# sensor_v60.net
KiCad netlist of a schematic drawn in EAGLE
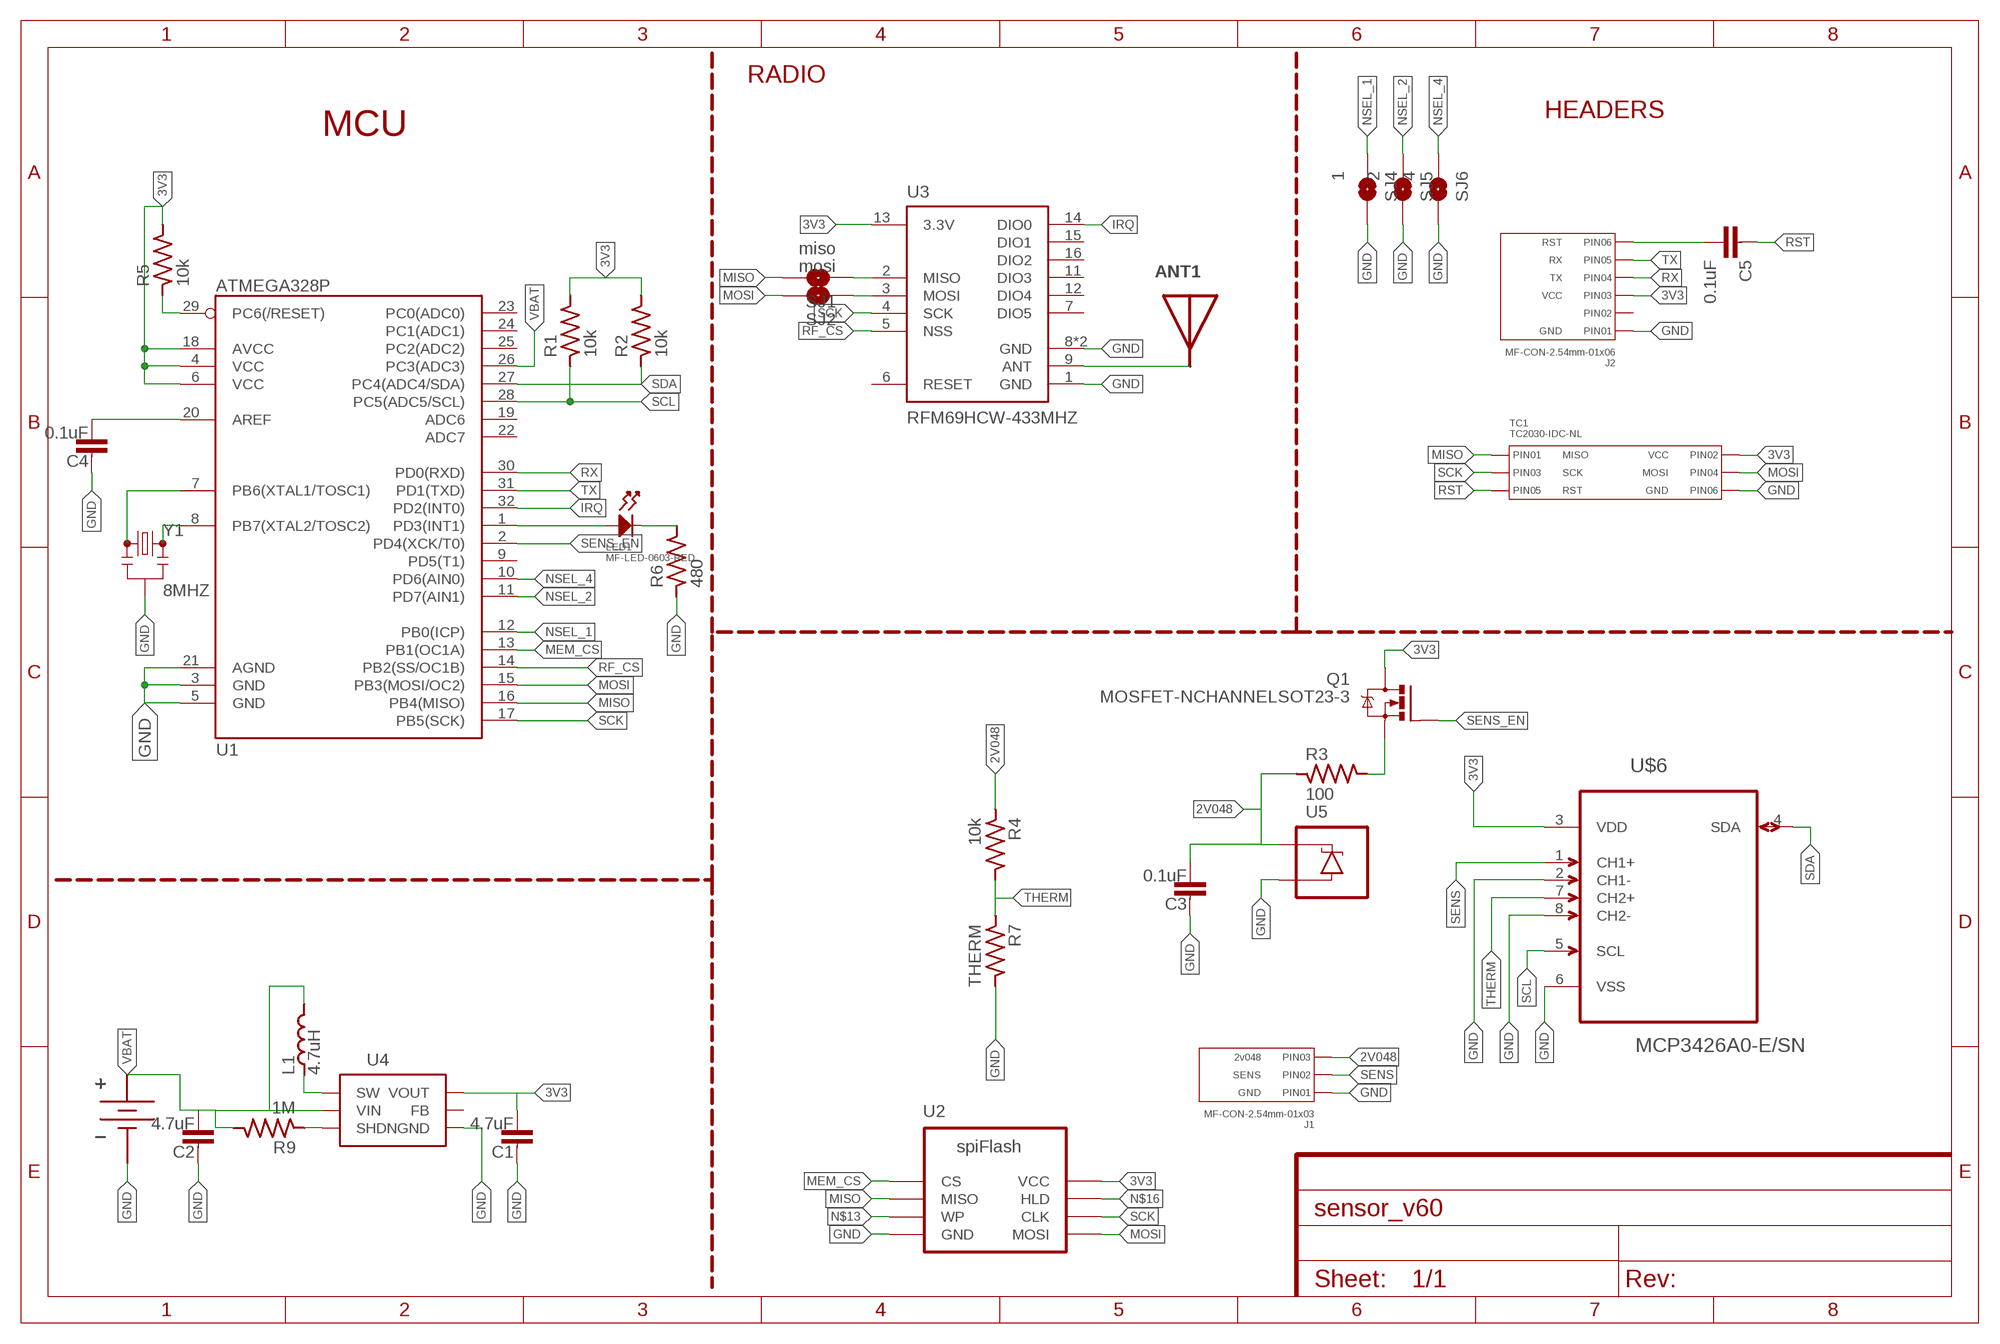
[diagram p0: schematic, sheet 1]

(export (version "E")
  (design (tool "Eeschema 10.0.6"))
  (components
    (comp (ref "ANT1")
      (value "ANTENNA-433_CHIP")
      (footprint "eagle-import:ANT_433_CHIP")
      (fields (field (name "PARTNO") "0433AT62A0020E"))
      (libsource (lib "eagle-import") (part "ANTENNA-433_CHIP"))
    )
    (comp (ref "C1")
      (value "4.7uF")
      (footprint "eagle-import:C0603-N")
      (libsource (lib "eagle-import") (part "CAPACITOR_NP0603-N"))
    )
    (comp (ref "C2")
      (value "4.7uF")
      (footprint "eagle-import:C0603-N")
      (libsource (lib "eagle-import") (part "CAPACITOR_NP0603-N"))
    )
    (comp (ref "C3")
      (value "0.1uF")
      (footprint "eagle-import:C0603-N")
      (libsource (lib "eagle-import") (part "CAPACITOR_NP0603-N"))
    )
    (comp (ref "C4")
      (value "0.1uF")
      (footprint "eagle-import:C0603-N")
      (libsource (lib "eagle-import") (part "CAPACITOR_NP0603-N"))
    )
    (comp (ref "C5")
      (value "0.1uF")
      (footprint "eagle-import:C0603-N")
      (libsource (lib "eagle-import") (part "CAPACITOR0603-N"))
    )
    (comp (ref "J1")
      (value "MF-CON-2.54mm-01x03")
      (footprint "eagle-import:PTH_2.54MM_01X03")
      (fields
        (field (name "HOUSEPART") "YES")
        (field (name "LABEL01") "GND")
        (field (name "LABEL02") "SENS")
        (field (name "LABEL03") "2v048")
        (field (name "PARTNO") "0022053031")
      )
      (libsource (lib "eagle-import") (part "CON_01X03_PTH_2.54MM"))
    )
    (comp (ref "J2")
      (value "MF-CON-2.54mm-01x06")
      (footprint "eagle-import:PTH_2.54MM_01X06")
      (fields
        (field (name "HOUSEPART") "YES")
        (field (name "LABEL01") "GND")
        (field (name "LABEL03") "VCC")
        (field (name "LABEL04") "TX")
        (field (name "LABEL05") "RX")
        (field (name "LABEL06") "RST")
      )
      (libsource (lib "eagle-import") (part "CON_01X06_PTH_2.54MM"))
    )
    (comp (ref "L1")
      (value "4.7uH")
      (footprint "eagle-import:L3030")
      (libsource (lib "eagle-import") (part "INDUCTOR3030"))
    )
    (comp (ref "LED1")
      (value "MF-LED-0603-RED")
      (footprint "eagle-import:LED0603")
      (fields (field (name "HOUSEPART") "YES"))
      (libsource (lib "eagle-import") (part "LED_SINGLE-0603-RED"))
    )
    (comp (ref "Q1")
      (value "MOSFET-NCHANNELSOT23-3")
      (footprint "eagle-import:SOT23-3")
      (libsource (lib "eagle-import") (part "MOSFET-NCHANNELSOT23-3"))
    )
    (comp (ref "R1")
      (value "10k")
      (footprint "eagle-import:R0603-N")
      (libsource (lib "eagle-import") (part "RESISTOR0603-N"))
    )
    (comp (ref "R2")
      (value "10k")
      (footprint "eagle-import:R0603-N")
      (libsource (lib "eagle-import") (part "RESISTOR0603-N"))
    )
    (comp (ref "R3")
      (value "100")
      (footprint "eagle-import:R0603-N")
      (libsource (lib "eagle-import") (part "RESISTOR0603-N"))
    )
    (comp (ref "R4")
      (value "10k")
      (footprint "eagle-import:R0603-N")
      (libsource (lib "eagle-import") (part "RESISTOR0603-N"))
    )
    (comp (ref "R5")
      (value "10k")
      (footprint "eagle-import:R0603-N")
      (libsource (lib "eagle-import") (part "RESISTOR0603-N"))
    )
    (comp (ref "R6")
      (value "480")
      (footprint "eagle-import:R0603-N")
      (libsource (lib "eagle-import") (part "RESISTOR0603-N"))
    )
    (comp (ref "R7")
      (value "THERM")
      (footprint "eagle-import:R0603-N")
      (fields (field (name "PARTNO") "FIND PART!!"))
      (libsource (lib "eagle-import") (part "RESISTOR0603-N"))
    )
    (comp (ref "R9")
      (value "1M")
      (footprint "eagle-import:R0603-N")
      (libsource (lib "eagle-import") (part "RESISTOR0603-N"))
    )
    (comp (ref "SJ1")
      (value "miso")
      (footprint "eagle-import:SJ_2S-NOTRACE")
      (libsource (lib "eagle-import") (part "SOLDERJUMPERNC2"))
    )
    (comp (ref "SJ2")
      (value "mosi")
      (footprint "eagle-import:SJ_2S-NOTRACE")
      (libsource (lib "eagle-import") (part "SOLDERJUMPERNC2"))
    )
    (comp (ref "SJ4")
      (value "1")
      (footprint "eagle-import:SJ_2S-NOTRACE")
      (libsource (lib "eagle-import") (part "SOLDERJUMPERNC2"))
    )
    (comp (ref "SJ5")
      (value "2")
      (footprint "eagle-import:SJ_2S-NOTRACE")
      (libsource (lib "eagle-import") (part "SOLDERJUMPERNC2"))
    )
    (comp (ref "SJ6")
      (value "4")
      (footprint "eagle-import:SJ_2S-NOTRACE")
      (libsource (lib "eagle-import") (part "SOLDERJUMPERNC2"))
    )
    (comp (ref "TC1")
      (value "TC2030-IDC-NL")
      (footprint "eagle-import:TC2030-IDC-NL")
      (fields (field (name "HOUSEPART") "NO") (field (name "PARTNO") "NA"))
      (libsource (lib "eagle-import") (part "CON_02X03_TC2030-IDC-NL_AVRISP"))
    )
    (comp (ref "U$1")
      (value "KEYSTONEAAHOLDER_2CELL")
      (footprint "eagle-import:KEYSTONEAAHOLDER_2CELL")
      (libsource (lib "eagle-import") (part "KEYSTONEAAHOLDER_2CELL"))
    )
    (comp (ref "U$6")
      (value "MCP3426A0-E/SN")
      (footprint "eagle-import:SOIC127P600X175-8N")
      (libsource (lib "eagle-import") (part "MCP3426A0-E/SN"))
    )
    (comp (ref "U1")
      (value "ATMEGA328P")
      (footprint "eagle-import:TQFP32")
      (libsource (lib "eagle-import") (part "ATMEGA328P_SMD-AU"))
    )
    (comp (ref "U2")
      (value "WINBOND_FLASH_4MBIT-SOIC")
      (footprint "eagle-import:SOIC8")
      (libsource (lib "eagle-import") (part "WINBOND_FLASH_4MBIT-SOIC"))
    )
    (comp (ref "U3")
      (value "RFM69HCW-433MHZ")
      (footprint "eagle-import:RFM69HCW-XXXS2")
      (fields (field (name "PARTNO") "COM-13910"))
      (libsource (lib "eagle-import") (part "RFM69HCW-433MHZ"))
    )
    (comp (ref "U4")
      (value "AAT1217-SOT23-6")
      (footprint "eagle-import:SOT23-6")
      (fields (field (name "PARTNO") "AAT1217ICA-3.3-T1"))
      (libsource (lib "eagle-import") (part "AAT1217-SOT23-6"))
    )
    (comp (ref "U5")
      (value "LM4040-SOT-23-3")
      (footprint "eagle-import:SOT23-3")
      (fields (field (name "PARTNO") "LM4040AIM3-2.0/NOPB "))
      (libsource (lib "eagle-import") (part "LM4040-SOT-23-3"))
    )
    (comp (ref "Y1")
      (value "8MHZ")
      (footprint "eagle-import:RESONATOR-SMD")
      (fields (field (name "PARTNO") "CSTCE8M00G55-R0"))
      (libsource (lib "eagle-import") (part "RESONATOR8MHZ"))
    )
  )
  (nets
    (net (code "1") (name "2V048") (class "Default")
      (node (ref "C3") (pin "2") (pinfunction "2_2") (pintype "passive"))
      (node (ref "J1") (pin "P$3") (pinfunction "PIN3_P$3") (pintype "bidirectional"))
      (node (ref "R3") (pin "1") (pinfunction "P$1_1") (pintype "passive"))
      (node (ref "R4") (pin "1") (pinfunction "P$1_1") (pintype "passive"))
      (node (ref "U5") (pin "1") (pinfunction "C_1") (pintype "bidirectional"))
    )
    (net (code "2") (name "3V3") (class "Default")
      (node (ref "C1") (pin "2") (pinfunction "2_2") (pintype "passive"))
      (node (ref "J2") (pin "P$3") (pinfunction "PIN3_P$3") (pintype "bidirectional"))
      (node (ref "Q1") (pin "3") (pinfunction "D_3") (pintype "passive"))
      (node (ref "R1") (pin "2") (pinfunction "P$2_2") (pintype "passive"))
      (node (ref "R2") (pin "2") (pinfunction "P$2_2") (pintype "passive"))
      (node (ref "R5") (pin "2") (pinfunction "P$2_2") (pintype "passive"))
      (node (ref "TC1") (pin "P$2") (pinfunction "PIN2_P$2") (pintype "bidirectional"))
      (node (ref "U$6") (pin "3") (pinfunction "VDD_3") (pintype "power_in"))
      (node (ref "U1") (pin "18") (pinfunction "AVCC_18") (pintype "bidirectional"))
      (node (ref "U1") (pin "4") (pinfunction "VCC_4") (pintype "bidirectional"))
      (node (ref "U1") (pin "6") (pinfunction "VCC_6") (pintype "bidirectional"))
      (node (ref "U2") (pin "8") (pinfunction "VCC_8") (pintype "bidirectional"))
      (node (ref "U3") (pin "13") (pinfunction "3.3V_13") (pintype "power_in"))
      (node (ref "U4") (pin "5") (pinfunction "VOUT_5") (pintype "bidirectional"))
    )
    (net (code "3") (name "GND") (class "Default")
      (node (ref "C1") (pin "1") (pinfunction "1_1") (pintype "passive"))
      (node (ref "C2") (pin "1") (pinfunction "1_1") (pintype "passive"))
      (node (ref "C3") (pin "1") (pinfunction "1_1") (pintype "passive"))
      (node (ref "C4") (pin "1") (pinfunction "1_1") (pintype "passive"))
      (node (ref "J1") (pin "P$1") (pinfunction "PIN1_P$1") (pintype "bidirectional"))
      (node (ref "J2") (pin "P$1") (pinfunction "PIN1_P$1") (pintype "bidirectional"))
      (node (ref "R6") (pin "1") (pinfunction "P$1_1") (pintype "passive"))
      (node (ref "R7") (pin "2") (pinfunction "P$2_2") (pintype "passive"))
      (node (ref "SJ4") (pin "2") (pinfunction "2_2") (pintype "passive"))
      (node (ref "SJ5") (pin "2") (pinfunction "2_2") (pintype "passive"))
      (node (ref "SJ6") (pin "2") (pinfunction "2_2") (pintype "passive"))
      (node (ref "TC1") (pin "P$6") (pinfunction "PIN6_P$6") (pintype "bidirectional"))
      (node (ref "U$1") (pin "P$2") (pinfunction "GND_P$2") (pintype "bidirectional"))
      (node (ref "U$6") (pin "2") (pinfunction "CH1-_2") (pintype "input"))
      (node (ref "U$6") (pin "6") (pinfunction "VSS_6") (pintype "power_in"))
      (node (ref "U$6") (pin "8") (pinfunction "CH2-_8") (pintype "input"))
      (node (ref "U1") (pin "21") (pinfunction "AGND_21") (pintype "bidirectional"))
      (node (ref "U1") (pin "3") (pinfunction "GND_3") (pintype "bidirectional"))
      (node (ref "U1") (pin "5") (pinfunction "GND_5") (pintype "bidirectional"))
      (node (ref "U2") (pin "4") (pinfunction "GND_4") (pintype "bidirectional"))
      (node (ref "U3") (pin "1") (pinfunction "GND_1") (pintype "power_in"))
      (node (ref "U3") (pin "10") (pinfunction "GND_10") (pintype "power_in"))
      (node (ref "U3") (pin "8") (pinfunction "GND_8") (pintype "power_in"))
      (node (ref "U4") (pin "2") (pinfunction "GND_2") (pintype "bidirectional"))
      (node (ref "U5") (pin "2") (pinfunction "A_2") (pintype "bidirectional"))
      (node (ref "Y1") (pin "2") (pinfunction "2_2") (pintype "passive"))
    )
    (net (code "4") (name "IRQ") (class "Default")
      (node (ref "U1") (pin "32") (pinfunction "PD2(INT0)_32") (pintype "bidirectional"))
      (node (ref "U3") (pin "14") (pinfunction "DIO0_14") (pintype "bidirectional"))
    )
    (net (code "5") (name "MEM_CS") (class "Default")
      (node (ref "U1") (pin "13") (pinfunction "PB1(OC1A)_13") (pintype "bidirectional"))
      (node (ref "U2") (pin "1") (pinfunction "CS_1") (pintype "bidirectional"))
    )
    (net (code "6") (name "MISO") (class "Default")
      (node (ref "SJ1") (pin "2") (pinfunction "2_2") (pintype "passive"))
      (node (ref "TC1") (pin "P$1") (pinfunction "PIN1_P$1") (pintype "bidirectional"))
      (node (ref "U1") (pin "16") (pinfunction "PB4(MISO)_16") (pintype "bidirectional"))
      (node (ref "U2") (pin "2") (pinfunction "MISO_2") (pintype "bidirectional"))
    )
    (net (code "7") (name "MOSI") (class "Default")
      (node (ref "SJ2") (pin "2") (pinfunction "2_2") (pintype "passive"))
      (node (ref "TC1") (pin "P$4") (pinfunction "PIN4_P$4") (pintype "bidirectional"))
      (node (ref "U1") (pin "15") (pinfunction "PB3(MOSI/OC2)_15") (pintype "bidirectional"))
      (node (ref "U2") (pin "5") (pinfunction "MOSI_5") (pintype "bidirectional"))
    )
    (net (code "8") (name "N$13") (class "Default")
      (node (ref "U2") (pin "3") (pinfunction "WP_3") (pintype "bidirectional"))
    )
    (net (code "9") (name "N$16") (class "Default")
      (node (ref "U2") (pin "7") (pinfunction "HLD_7") (pintype "bidirectional"))
    )
    (net (code "10") (name "NSEL_1") (class "Default")
      (node (ref "SJ4") (pin "1") (pinfunction "1_1") (pintype "passive"))
      (node (ref "U1") (pin "12") (pinfunction "PB0(ICP)_12") (pintype "bidirectional"))
    )
    (net (code "11") (name "NSEL_2") (class "Default")
      (node (ref "SJ5") (pin "1") (pinfunction "1_1") (pintype "passive"))
      (node (ref "U1") (pin "11") (pinfunction "PD7(AIN1)_11") (pintype "bidirectional"))
    )
    (net (code "12") (name "NSEL_4") (class "Default")
      (node (ref "SJ6") (pin "1") (pinfunction "1_1") (pintype "passive"))
      (node (ref "U1") (pin "10") (pinfunction "PD6(AIN0)_10") (pintype "bidirectional"))
    )
    (net (code "13") (name "Net-(J2-PIN6)") (class "Default")
      (node (ref "C5") (pin "2") (pinfunction "2_2") (pintype "passive"))
      (node (ref "J2") (pin "P$6") (pinfunction "PIN6_P$6") (pintype "bidirectional"))
    )
    (net (code "14") (name "Net-(Q1-S)") (class "Default")
      (node (ref "Q1") (pin "2") (pinfunction "S_2") (pintype "passive"))
      (node (ref "R3") (pin "2") (pinfunction "P$2_2") (pintype "passive"))
    )
    (net (code "15") (name "Net-(R6-P$2)") (class "Default")
      (node (ref "LED1") (pin "CATHODE") (pinfunction "CATHODE_CATHODE") (pintype "power_in"))
      (node (ref "R6") (pin "2") (pinfunction "P$2_2") (pintype "passive"))
    )
    (net (code "16") (name "Net-(R9-P$1)") (class "Default")
      (node (ref "R9") (pin "1") (pinfunction "P$1_1") (pintype "passive"))
      (node (ref "U4") (pin "4") (pinfunction "SHDN_4") (pintype "bidirectional"))
    )
    (net (code "17") (name "Net-(U1-AREF)") (class "Default")
      (node (ref "C4") (pin "2") (pinfunction "2_2") (pintype "passive"))
      (node (ref "U1") (pin "20") (pinfunction "AREF_20") (pintype "bidirectional"))
    )
    (net (code "18") (name "Net-(U1-PB6(XTAL1{slash}TOSC1))") (class "Default")
      (node (ref "U1") (pin "7") (pinfunction "PB6(XTAL1/TOSC1)_7") (pintype "bidirectional"))
      (node (ref "Y1") (pin "1") (pinfunction "1_1") (pintype "passive"))
    )
    (net (code "19") (name "Net-(U1-PB7(XTAL2{slash}TOSC2))") (class "Default")
      (node (ref "U1") (pin "8") (pinfunction "PB7(XTAL2/TOSC2)_8") (pintype "bidirectional"))
      (node (ref "Y1") (pin "3") (pinfunction "3_3") (pintype "passive"))
    )
    (net (code "20") (name "Net-(U1-PD3(INT1))") (class "Default")
      (node (ref "LED1") (pin "ANODE") (pinfunction "ANODE_ANODE") (pintype "power_in"))
      (node (ref "U1") (pin "1") (pinfunction "PD3(INT1)_1") (pintype "bidirectional"))
    )
    (net (code "21") (name "Net-(U3-ANT)") (class "Default")
      (node (ref "ANT1") (pin "1") (pinfunction "1_1") (pintype "bidirectional"))
      (node (ref "U3") (pin "9") (pinfunction "ANT_9") (pintype "passive"))
    )
    (net (code "22") (name "Net-(U3-MISO)") (class "Default")
      (node (ref "SJ1") (pin "1") (pinfunction "1_1") (pintype "passive"))
      (node (ref "U3") (pin "2") (pinfunction "MISO_2") (pintype "bidirectional"))
    )
    (net (code "23") (name "Net-(U3-MOSI)") (class "Default")
      (node (ref "SJ2") (pin "1") (pinfunction "1_1") (pintype "passive"))
      (node (ref "U3") (pin "3") (pinfunction "MOSI_3") (pintype "input"))
    )
    (net (code "24") (name "Net-(U4-SW)") (class "Default")
      (node (ref "L1") (pin "P$1") (pinfunction "P$1_P$1") (pintype "passive"))
      (node (ref "U4") (pin "1") (pinfunction "SW_1") (pintype "bidirectional"))
    )
    (net (code "25") (name "RF_CS") (class "Default")
      (node (ref "U1") (pin "14") (pinfunction "PB2(SS/OC1B)_14") (pintype "bidirectional"))
      (node (ref "U3") (pin "5") (pinfunction "NSS_5") (pintype "input"))
    )
    (net (code "26") (name "RST") (class "Default")
      (node (ref "C5") (pin "1") (pinfunction "1_1") (pintype "passive"))
      (node (ref "R5") (pin "1") (pinfunction "P$1_1") (pintype "passive"))
      (node (ref "TC1") (pin "P$5") (pinfunction "PIN5_P$5") (pintype "bidirectional"))
      (node (ref "U1") (pin "29") (pinfunction "PC6(/RESET)_29") (pintype "bidirectional"))
    )
    (net (code "27") (name "RX") (class "Default")
      (node (ref "J2") (pin "P$4") (pinfunction "PIN4_P$4") (pintype "bidirectional"))
      (node (ref "U1") (pin "30") (pinfunction "PD0(RXD)_30") (pintype "bidirectional"))
    )
    (net (code "28") (name "SCK") (class "Default")
      (node (ref "TC1") (pin "P$3") (pinfunction "PIN3_P$3") (pintype "bidirectional"))
      (node (ref "U1") (pin "17") (pinfunction "PB5(SCK)_17") (pintype "bidirectional"))
      (node (ref "U2") (pin "6") (pinfunction "CLK_6") (pintype "bidirectional"))
      (node (ref "U3") (pin "4") (pinfunction "SCK_4") (pintype "input"))
    )
    (net (code "29") (name "SCL") (class "Default")
      (node (ref "R1") (pin "1") (pinfunction "P$1_1") (pintype "passive"))
      (node (ref "U$6") (pin "5") (pinfunction "SCL_5") (pintype "input"))
      (node (ref "U1") (pin "28") (pinfunction "PC5(ADC5/SCL)_28") (pintype "bidirectional"))
    )
    (net (code "30") (name "SDA") (class "Default")
      (node (ref "R2") (pin "1") (pinfunction "P$1_1") (pintype "passive"))
      (node (ref "U$6") (pin "4") (pinfunction "SDA_4") (pintype "bidirectional"))
      (node (ref "U1") (pin "27") (pinfunction "PC4(ADC4/SDA)_27") (pintype "bidirectional"))
    )
    (net (code "31") (name "SENS") (class "Default")
      (node (ref "J1") (pin "P$2") (pinfunction "PIN2_P$2") (pintype "bidirectional"))
      (node (ref "U$6") (pin "1") (pinfunction "CH1+_1") (pintype "input"))
    )
    (net (code "32") (name "SENS_EN") (class "Default")
      (node (ref "Q1") (pin "1") (pinfunction "G_1") (pintype "passive"))
      (node (ref "U1") (pin "2") (pinfunction "PD4(XCK/T0)_2") (pintype "bidirectional"))
    )
    (net (code "33") (name "THERM") (class "Default")
      (node (ref "R4") (pin "2") (pinfunction "P$2_2") (pintype "passive"))
      (node (ref "R7") (pin "1") (pinfunction "P$1_1") (pintype "passive"))
      (node (ref "U$6") (pin "7") (pinfunction "CH2+_7") (pintype "input"))
    )
    (net (code "34") (name "TX") (class "Default")
      (node (ref "J2") (pin "P$5") (pinfunction "PIN5_P$5") (pintype "bidirectional"))
      (node (ref "U1") (pin "31") (pinfunction "PD1(TXD)_31") (pintype "bidirectional"))
    )
    (net (code "35") (name "VBAT") (class "Default")
      (node (ref "C2") (pin "2") (pinfunction "2_2") (pintype "passive"))
      (node (ref "L1") (pin "P$2") (pinfunction "P$2_P$2") (pintype "passive"))
      (node (ref "R9") (pin "2") (pinfunction "P$2_2") (pintype "passive"))
      (node (ref "U$1") (pin "P$1") (pinfunction "VBAT_P$1") (pintype "bidirectional"))
      (node (ref "U1") (pin "26") (pinfunction "PC3(ADC3)_26") (pintype "bidirectional"))
      (node (ref "U4") (pin "6") (pinfunction "VIN_6") (pintype "bidirectional"))
    )
    (net (code "36") (name "unconnected-(J2-PIN2-PadP$2)") (class "Default")
      (node (ref "J2") (pin "P$2") (pinfunction "PIN2_P$2") (pintype "bidirectional"))
    )
    (net (code "37") (name "unconnected-(U1-ADC6-Pad19)") (class "Default")
      (node (ref "U1") (pin "19") (pinfunction "ADC6_19") (pintype "bidirectional"))
    )
    (net (code "38") (name "unconnected-(U1-ADC7-Pad22)") (class "Default")
      (node (ref "U1") (pin "22") (pinfunction "ADC7_22") (pintype "bidirectional"))
    )
    (net (code "39") (name "unconnected-(U1-PC0(ADC0)-Pad23)") (class "Default")
      (node (ref "U1") (pin "23") (pinfunction "PC0(ADC0)_23") (pintype "bidirectional"))
    )
    (net (code "40") (name "unconnected-(U1-PC1(ADC1)-Pad24)") (class "Default")
      (node (ref "U1") (pin "24") (pinfunction "PC1(ADC1)_24") (pintype "bidirectional"))
    )
    (net (code "41") (name "unconnected-(U1-PC2(ADC2)-Pad25)") (class "Default")
      (node (ref "U1") (pin "25") (pinfunction "PC2(ADC2)_25") (pintype "bidirectional"))
    )
    (net (code "42") (name "unconnected-(U1-PD5(T1)-Pad9)") (class "Default")
      (node (ref "U1") (pin "9") (pinfunction "PD5(T1)_9") (pintype "bidirectional"))
    )
    (net (code "43") (name "unconnected-(U3-DIO1-Pad15)") (class "Default")
      (node (ref "U3") (pin "15") (pinfunction "DIO1_15") (pintype "bidirectional"))
    )
    (net (code "44") (name "unconnected-(U3-DIO2-Pad16)") (class "Default")
      (node (ref "U3") (pin "16") (pinfunction "DIO2_16") (pintype "bidirectional"))
    )
    (net (code "45") (name "unconnected-(U3-DIO3-Pad11)") (class "Default")
      (node (ref "U3") (pin "11") (pinfunction "DIO3_11") (pintype "bidirectional"))
    )
    (net (code "46") (name "unconnected-(U3-DIO4-Pad12)") (class "Default")
      (node (ref "U3") (pin "12") (pinfunction "DIO4_12") (pintype "bidirectional"))
    )
    (net (code "47") (name "unconnected-(U3-DIO5-Pad7)") (class "Default")
      (node (ref "U3") (pin "7") (pinfunction "DIO5_7") (pintype "bidirectional"))
    )
    (net (code "48") (name "unconnected-(U3-RESET-Pad6)") (class "Default")
      (node (ref "U3") (pin "6") (pinfunction "RESET_6") (pintype "input"))
    )
    (net (code "49") (name "unconnected-(U4-FB-Pad3)") (class "Default")
      (node (ref "U4") (pin "3") (pinfunction "FB_3") (pintype "bidirectional"))
    )
  )
)
